# Trap_Lighting_Programmable_SpectrumV03B.net
KiCad netlist of a schematic drawn in EAGLE
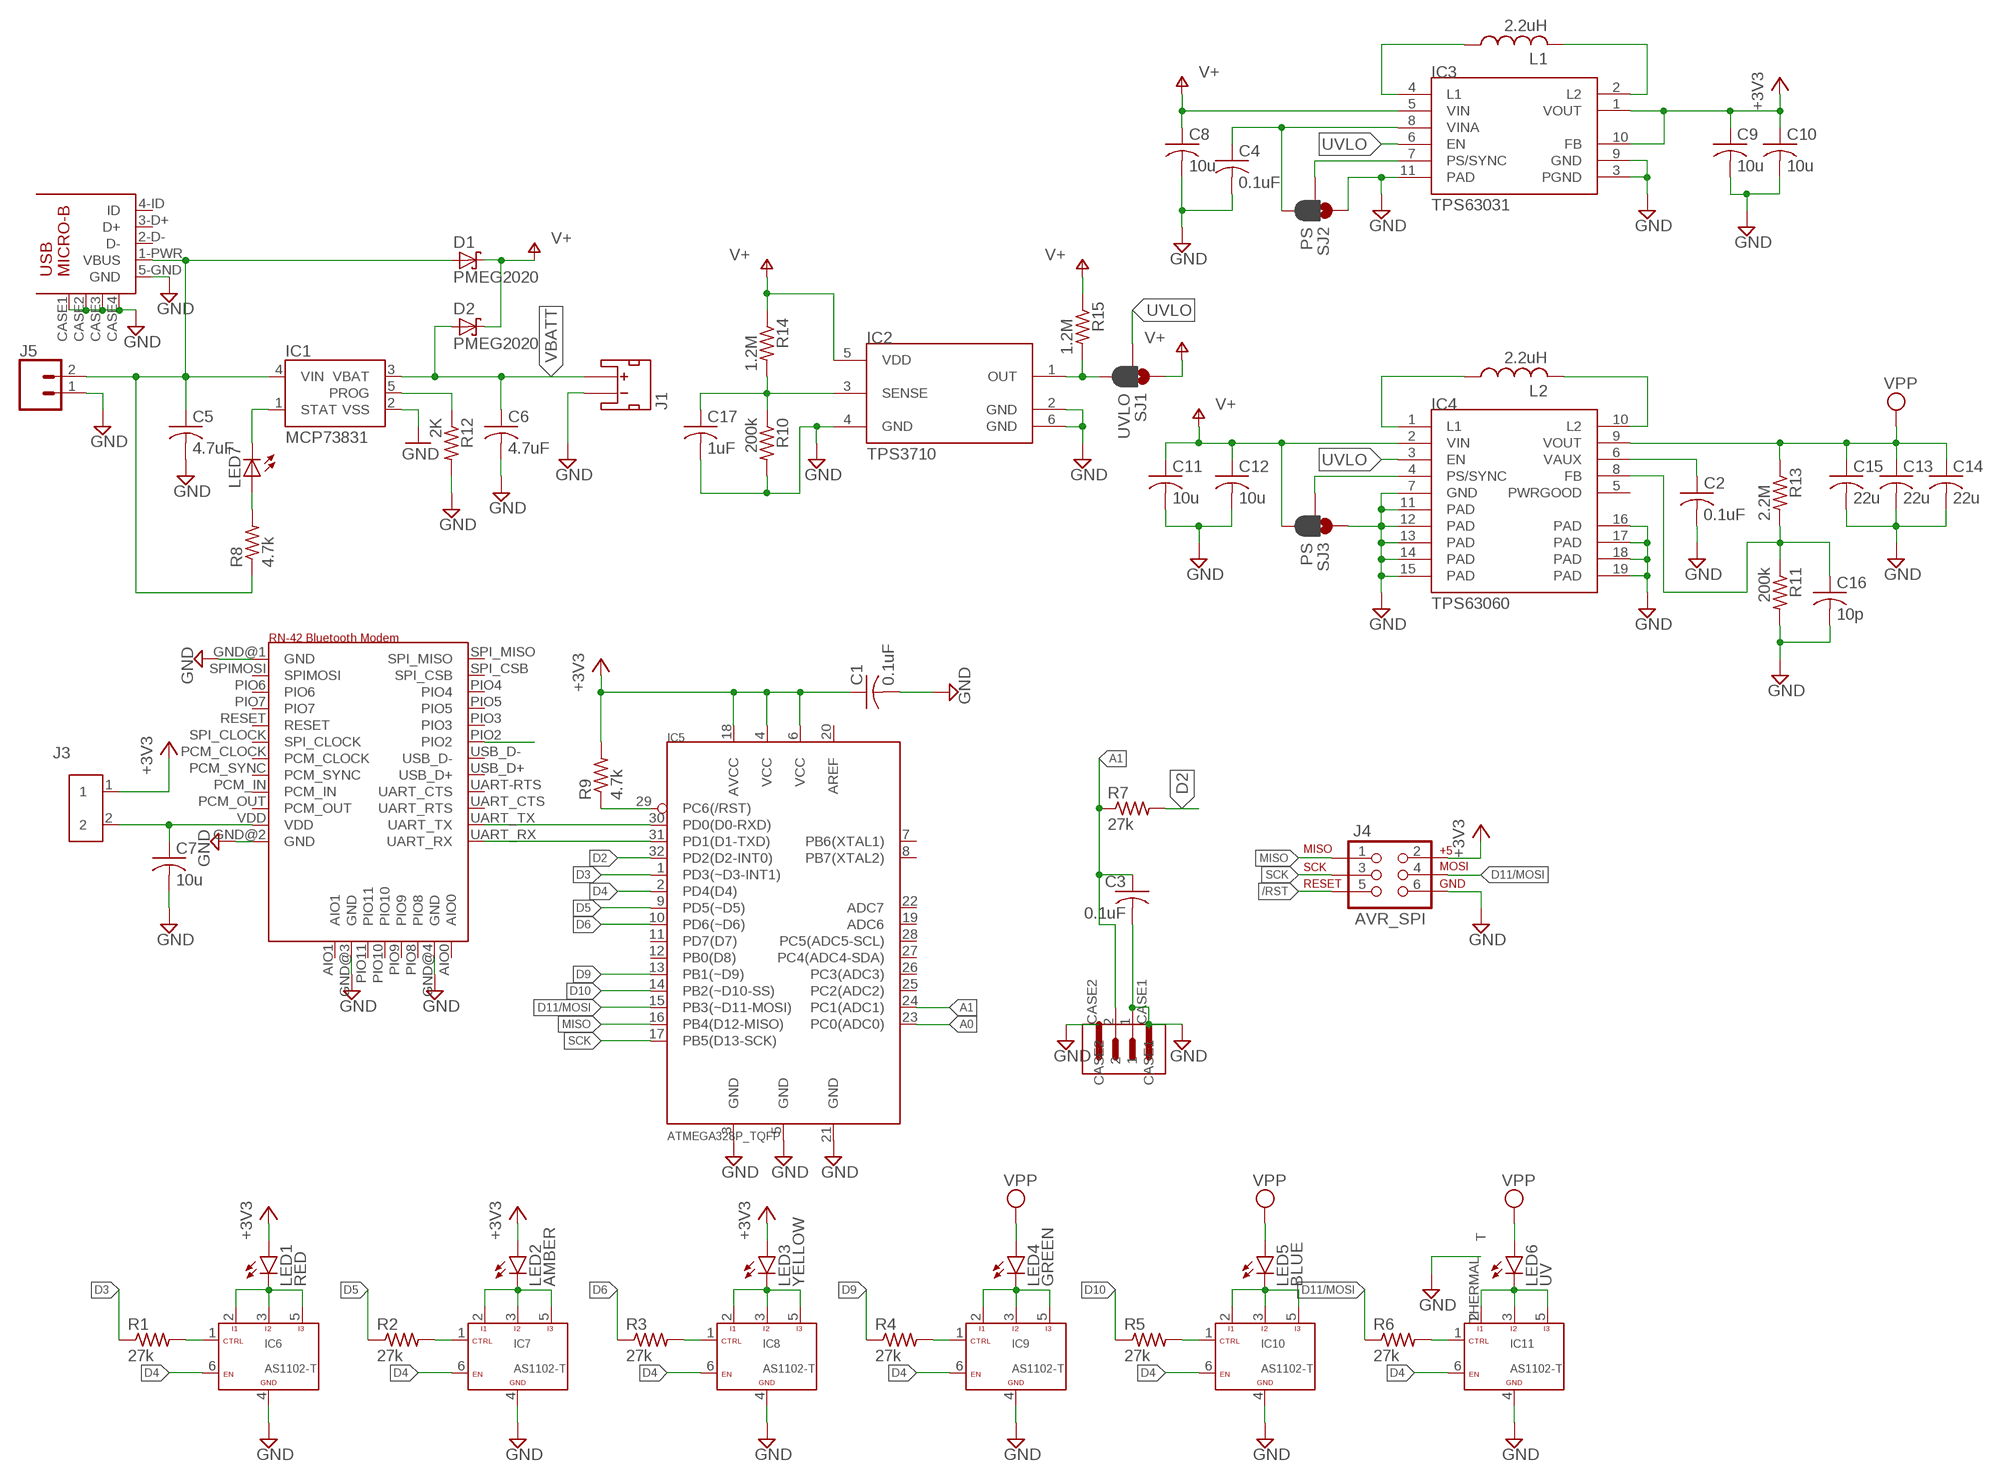
[diagram p0: schematic, sheet 1]

(export (version "E")
  (design (tool "Eeschema 10.0.6"))
  (components
    (comp (ref "A1")
      (value "RN-42_BLUETOOTH")
      (footprint "eagle-import:RN-42")
      (libsource (lib "eagle-import") (part "RN-42_BLUETOOTH"))
    )
    (comp (ref "C1")
      (value "0.1uF")
      (footprint "eagle-import:C0805")
      (libsource (lib "eagle-import") (part "C-USC0805"))
    )
    (comp (ref "C2")
      (value "0.1uF")
      (footprint "eagle-import:C0805")
      (libsource (lib "eagle-import") (part "C-USC0805"))
    )
    (comp (ref "C3")
      (value "0.1uF")
      (footprint "eagle-import:C0805")
      (libsource (lib "eagle-import") (part "C-USC0805"))
    )
    (comp (ref "C4")
      (value "0.1uF")
      (footprint "eagle-import:C0805")
      (libsource (lib "eagle-import") (part "C-USC0805"))
    )
    (comp (ref "C5")
      (value "4.7uF")
      (footprint "eagle-import:C0805")
      (libsource (lib "eagle-import") (part "C-USC0805"))
    )
    (comp (ref "C6")
      (value "4.7uF")
      (footprint "eagle-import:C0805")
      (libsource (lib "eagle-import") (part "C-USC0805"))
    )
    (comp (ref "C7")
      (value "10u")
      (footprint "eagle-import:C0805")
      (libsource (lib "eagle-import") (part "C-USC0805"))
    )
    (comp (ref "C8")
      (value "10u")
      (footprint "eagle-import:C0805")
      (libsource (lib "eagle-import") (part "C-USC0805"))
    )
    (comp (ref "C9")
      (value "10u")
      (footprint "eagle-import:C0805")
      (libsource (lib "eagle-import") (part "C-USC0805"))
    )
    (comp (ref "C10")
      (value "10u")
      (footprint "eagle-import:C0805")
      (libsource (lib "eagle-import") (part "C-USC0805"))
    )
    (comp (ref "C11")
      (value "10u")
      (footprint "eagle-import:C0805")
      (libsource (lib "eagle-import") (part "C-USC0805"))
    )
    (comp (ref "C12")
      (value "10u")
      (footprint "eagle-import:C0805")
      (libsource (lib "eagle-import") (part "C-USC0805"))
    )
    (comp (ref "C13")
      (value "22u")
      (footprint "eagle-import:C1206")
      (libsource (lib "eagle-import") (part "rcl_334_C-USC1206"))
    )
    (comp (ref "C14")
      (value "22u")
      (footprint "eagle-import:C1206")
      (libsource (lib "eagle-import") (part "rcl_334_C-USC1206"))
    )
    (comp (ref "C15")
      (value "22u")
      (footprint "eagle-import:C1206")
      (libsource (lib "eagle-import") (part "rcl_334_C-USC1206"))
    )
    (comp (ref "C16")
      (value "10p")
      (footprint "eagle-import:C0805")
      (libsource (lib "eagle-import") (part "C-USC0805"))
    )
    (comp (ref "C17")
      (value "1uF")
      (footprint "eagle-import:C0805")
      (libsource (lib "eagle-import") (part "C-USC0805"))
    )
    (comp (ref "D1")
      (value "PMEG2020")
      (footprint "eagle-import:SOD323_ST")
      (libsource (lib "eagle-import") (part "BAT60J"))
    )
    (comp (ref "D2")
      (value "PMEG2020")
      (footprint "eagle-import:SOD323_ST")
      (libsource (lib "eagle-import") (part "BAT60J"))
    )
    (comp (ref "IC1")
      (value "MCP73831")
      (footprint "eagle-import:SOT23-5")
      (libsource (lib "eagle-import") (part "MCP73831SMD"))
    )
    (comp (ref "IC2")
      (value "TPS3710")
      (footprint "eagle-import:SOT6")
      (libsource (lib "eagle-import") (part "TPS3710"))
    )
    (comp (ref "IC3")
      (value "TPS63031")
      (footprint "eagle-import:VSON-10")
      (libsource (lib "eagle-import") (part "TPS63031"))
    )
    (comp (ref "IC4")
      (value "TPS63060")
      (footprint "eagle-import:WSON1-10")
      (libsource (lib "eagle-import") (part "TPS63060"))
    )
    (comp (ref "IC5")
      (value "ATMEGA328P_TQFP")
      (footprint "eagle-import:TQFP-32")
      (libsource (lib "eagle-import") (part "ATMEGA328P_TQFP"))
    )
    (comp (ref "IC6")
      (value "AS1102-T")
      (footprint "eagle-import:SC70-6")
      (libsource (lib "eagle-import") (part "AS1102-T"))
    )
    (comp (ref "IC7")
      (value "AS1102-T")
      (footprint "eagle-import:SC70-6")
      (libsource (lib "eagle-import") (part "AS1102-T"))
    )
    (comp (ref "IC8")
      (value "AS1102-T")
      (footprint "eagle-import:SC70-6")
      (libsource (lib "eagle-import") (part "AS1102-T"))
    )
    (comp (ref "IC9")
      (value "AS1102-T")
      (footprint "eagle-import:SC70-6")
      (libsource (lib "eagle-import") (part "AS1102-T"))
    )
    (comp (ref "IC10")
      (value "AS1102-T")
      (footprint "eagle-import:SC70-6")
      (libsource (lib "eagle-import") (part "AS1102-T"))
    )
    (comp (ref "IC11")
      (value "AS1102-T")
      (footprint "eagle-import:SC70-6")
      (libsource (lib "eagle-import") (part "AS1102-T"))
    )
    (comp (ref "J1")
      (value "JST_2MM_MALE")
      (footprint "eagle-import:JST-2-SMD")
      (libsource (lib "eagle-import") (part "JST_2MM_MALE"))
    )
    (comp (ref "J2")
      (value "2PIN_SMD_PHOENIX_CONTACTVERTICAL_PACKAGE")
      (footprint "eagle-import:2-PIN-VERT-PHOENIX_SMD")
      (libsource (lib "eagle-import") (part "2PIN_SMD_PHOENIX_CONTACTVERTICAL_PACKAGE"))
    )
    (comp (ref "J3")
      (value "2MM_SMD_M_HEADER")
      (footprint "eagle-import:2MM_MALE_SMD_HEADER")
      (libsource (lib "eagle-import") (part "2MM_SMD_M_HEADER"))
    )
    (comp (ref "J4")
      (value "AVR_SPI")
      (footprint "eagle-import:2X3")
      (libsource (lib "eagle-import") (part "AVR_SPI_PRG_6PTH"))
    )
    (comp (ref "J5")
      (value "CONN_02PTH3")
      (footprint "eagle-import:1X02_LONGPADS")
      (libsource (lib "eagle-import") (part "CONN_02PTH3"))
    )
    (comp (ref "L1")
      (value "2.2uH")
      (footprint "eagle-import:VLF302512MT-2R2M-CA_INDUCTOR")
      (libsource (lib "eagle-import") (part "VLF302512MT-2R2M-CA_INDUCTOR"))
    )
    (comp (ref "L2")
      (value "2.2uH")
      (footprint "eagle-import:VLF302512MT-2R2M-CA_INDUCTOR")
      (libsource (lib "eagle-import") (part "VLF302512MT-2R2M-CA_INDUCTOR"))
    )
    (comp (ref "LED1")
      (value "RED")
      (footprint "eagle-import:LED_TT_OVS5MX")
      (libsource (lib "eagle-import") (part "LED_TT_OVS5MXTT_OVS5MX"))
    )
    (comp (ref "LED2")
      (value "AMBER")
      (footprint "eagle-import:LED_TT_OVS5MX")
      (libsource (lib "eagle-import") (part "LED_TT_OVS5MXTT_OVS5MX"))
    )
    (comp (ref "LED3")
      (value "YELLOW")
      (footprint "eagle-import:LED_TT_OVS5MX")
      (libsource (lib "eagle-import") (part "LED_TT_OVS5MXTT_OVS5MX"))
    )
    (comp (ref "LED4")
      (value "GREEN")
      (footprint "eagle-import:LED_LUXEON_3535L")
      (libsource (lib "eagle-import") (part "LED_TT_OVS5MXLUXEON_3535L"))
    )
    (comp (ref "LED5")
      (value "BLUE")
      (footprint "eagle-import:LED_TT_OVS5MX")
      (libsource (lib "eagle-import") (part "LED_TT_OVS5MXTT_OVS5MX"))
    )
    (comp (ref "LED6")
      (value "UV")
      (footprint "eagle-import:LED_LITEON_CO3_UV")
      (libsource (lib "eagle-import") (part "LITEON_CO34UV_LED"))
    )
    (comp (ref "LED7")
      (value "LEDCHIPLED_0805")
      (footprint "eagle-import:CHIPLED_0805")
      (libsource (lib "eagle-import") (part "LEDCHIPLED_0805"))
    )
    (comp (ref "R1")
      (value "27k")
      (footprint "eagle-import:R0805")
      (libsource (lib "eagle-import") (part "R-US_R0805"))
    )
    (comp (ref "R2")
      (value "27k")
      (footprint "eagle-import:R0805")
      (libsource (lib "eagle-import") (part "R-US_R0805"))
    )
    (comp (ref "R3")
      (value "27k")
      (footprint "eagle-import:R0805")
      (libsource (lib "eagle-import") (part "R-US_R0805"))
    )
    (comp (ref "R4")
      (value "27k")
      (footprint "eagle-import:R0805")
      (libsource (lib "eagle-import") (part "R-US_R0805"))
    )
    (comp (ref "R5")
      (value "27k")
      (footprint "eagle-import:R0805")
      (libsource (lib "eagle-import") (part "R-US_R0805"))
    )
    (comp (ref "R6")
      (value "27k")
      (footprint "eagle-import:R0805")
      (libsource (lib "eagle-import") (part "R-US_R0805"))
    )
    (comp (ref "R7")
      (value "27k")
      (footprint "eagle-import:R0805")
      (libsource (lib "eagle-import") (part "R-US_R0805"))
    )
    (comp (ref "R8")
      (value "4.7k")
      (footprint "eagle-import:R0805")
      (libsource (lib "eagle-import") (part "R-US_R0805"))
    )
    (comp (ref "R9")
      (value "4.7k")
      (footprint "eagle-import:R0805")
      (libsource (lib "eagle-import") (part "R-US_R0805"))
    )
    (comp (ref "R10")
      (value "200k")
      (footprint "eagle-import:R0805")
      (libsource (lib "eagle-import") (part "R-US_R0805"))
    )
    (comp (ref "R11")
      (value "200k")
      (footprint "eagle-import:R0805")
      (libsource (lib "eagle-import") (part "R-US_R0805"))
    )
    (comp (ref "R12")
      (value "2K")
      (footprint "eagle-import:R0805")
      (libsource (lib "eagle-import") (part "R-US_R0805"))
    )
    (comp (ref "R13")
      (value "2.2M")
      (footprint "eagle-import:R0805")
      (libsource (lib "eagle-import") (part "R-US_R0805"))
    )
    (comp (ref "R14")
      (value "1.2M")
      (footprint "eagle-import:R0805")
      (libsource (lib "eagle-import") (part "R-US_R0805"))
    )
    (comp (ref "R15")
      (value "1.2M")
      (footprint "eagle-import:R0805")
      (libsource (lib "eagle-import") (part "R-US_R0805"))
    )
    (comp (ref "SJ1")
      (value "UVLO")
      (footprint "eagle-import:SMT-JUMPER_3_1-NC_PASTE_SILK")
      (libsource (lib "eagle-import") (part "JUMPER-SMT_3_1-NC_PASTE_SILK"))
    )
    (comp (ref "SJ2")
      (value "PS")
      (footprint "eagle-import:SMT-JUMPER_3_1-NC_PASTE_SILK")
      (libsource (lib "eagle-import") (part "JUMPER-SMT_3_1-NC_PASTE_SILK"))
    )
    (comp (ref "SJ3")
      (value "PS")
      (footprint "eagle-import:SMT-JUMPER_3_1-NC_PASTE_SILK")
      (libsource (lib "eagle-import") (part "JUMPER-SMT_3_1-NC_PASTE_SILK"))
    )
    (comp (ref "USB1")
      (value "USB-MICRO-B")
      (footprint "eagle-import:USB_MICRO_B_WURTH_629105136821")
      (libsource (lib "eagle-import") (part "USB-MICRO-B"))
    )
  )
  (nets
    (net (code "1") (name "+3V3") (class "Default")
      (node (ref "C1") (pin "1") (pinfunction "1_1") (pintype "passive"))
      (node (ref "C10") (pin "1") (pinfunction "1_1") (pintype "passive"))
      (node (ref "C9") (pin "1") (pinfunction "1_1") (pintype "passive"))
      (node (ref "IC3") (pin "1") (pinfunction "VOUT_1") (pintype "passive"))
      (node (ref "IC3") (pin "10") (pinfunction "FB_10") (pintype "passive"))
      (node (ref "IC5") (pin "18") (pinfunction "AVCC_18") (pintype "bidirectional"))
      (node (ref "IC5") (pin "4") (pinfunction "VCC_4") (pintype "bidirectional"))
      (node (ref "IC5") (pin "6") (pinfunction "VCC_6") (pintype "bidirectional"))
      (node (ref "J3") (pin "1") (pinfunction "1_1") (pintype "bidirectional"))
      (node (ref "J4") (pin "2") (pinfunction "2_2") (pintype "passive"))
      (node (ref "LED1") (pin "A") (pinfunction "A_A") (pintype "passive"))
      (node (ref "LED2") (pin "A") (pinfunction "A_A") (pintype "passive"))
      (node (ref "LED3") (pin "A") (pinfunction "A_A") (pintype "passive"))
      (node (ref "R9") (pin "2") (pinfunction "2_2") (pintype "passive"))
    )
    (net (code "2") (name "A0") (class "Default")
      (node (ref "IC5") (pin "23") (pinfunction "PC0(ADC0)_23") (pintype "bidirectional"))
    )
    (net (code "3") (name "A1") (class "Default")
      (node (ref "C3") (pin "1") (pinfunction "1_1") (pintype "passive"))
      (node (ref "IC5") (pin "24") (pinfunction "PC1(ADC1)_24") (pintype "bidirectional"))
      (node (ref "J2") (pin "2") (pinfunction "2_2") (pintype "bidirectional"))
      (node (ref "R7") (pin "1") (pinfunction "1_1") (pintype "passive"))
    )
    (net (code "4") (name "D2") (class "Default")
      (node (ref "IC5") (pin "32") (pinfunction "PD2(D2-INT0)_32") (pintype "bidirectional"))
      (node (ref "R7") (pin "2") (pinfunction "2_2") (pintype "passive"))
    )
    (net (code "5") (name "D3") (class "Default")
      (node (ref "IC5") (pin "1") (pinfunction "PD3(~{D3-INT1})_1") (pintype "bidirectional"))
      (node (ref "R1") (pin "1") (pinfunction "1_1") (pintype "passive"))
    )
    (net (code "6") (name "D4") (class "Default")
      (node (ref "IC10") (pin "6") (pinfunction "EN_6") (pintype "bidirectional"))
      (node (ref "IC11") (pin "6") (pinfunction "EN_6") (pintype "bidirectional"))
      (node (ref "IC5") (pin "2") (pinfunction "PD4(D4)_2") (pintype "bidirectional"))
      (node (ref "IC6") (pin "6") (pinfunction "EN_6") (pintype "bidirectional"))
      (node (ref "IC7") (pin "6") (pinfunction "EN_6") (pintype "bidirectional"))
      (node (ref "IC8") (pin "6") (pinfunction "EN_6") (pintype "bidirectional"))
      (node (ref "IC9") (pin "6") (pinfunction "EN_6") (pintype "bidirectional"))
    )
    (net (code "7") (name "D5") (class "Default")
      (node (ref "IC5") (pin "9") (pinfunction "PD5(~{D5})_9") (pintype "bidirectional"))
      (node (ref "R2") (pin "1") (pinfunction "1_1") (pintype "passive"))
    )
    (net (code "8") (name "D6") (class "Default")
      (node (ref "IC5") (pin "10") (pinfunction "PD6(~{D6})_10") (pintype "bidirectional"))
      (node (ref "R3") (pin "1") (pinfunction "1_1") (pintype "passive"))
    )
    (net (code "9") (name "D9") (class "Default")
      (node (ref "IC5") (pin "13") (pinfunction "PB1(~{D9})_13") (pintype "bidirectional"))
      (node (ref "R4") (pin "1") (pinfunction "1_1") (pintype "passive"))
    )
    (net (code "10") (name "D10") (class "Default")
      (node (ref "IC5") (pin "14") (pinfunction "PB2(~{D10-SS})_14") (pintype "bidirectional"))
      (node (ref "R5") (pin "1") (pinfunction "1_1") (pintype "passive"))
    )
    (net (code "11") (name "D11{slash}MOSI") (class "Default")
      (node (ref "IC5") (pin "15") (pinfunction "PB3(~{D11-MOSI})_15") (pintype "bidirectional"))
      (node (ref "J4") (pin "4") (pinfunction "4_4") (pintype "passive"))
      (node (ref "R6") (pin "1") (pinfunction "1_1") (pintype "passive"))
    )
    (net (code "12") (name "GND") (class "Default")
      (node (ref "A1") (pin "GND@1") (pinfunction "GND_GND@1") (pintype "bidirectional"))
      (node (ref "A1") (pin "GND@2") (pinfunction "GND_GND@2") (pintype "bidirectional"))
      (node (ref "A1") (pin "GND@3") (pinfunction "GND_GND@3") (pintype "bidirectional"))
      (node (ref "A1") (pin "GND@4") (pinfunction "GND_GND@4") (pintype "bidirectional"))
      (node (ref "C1") (pin "2") (pinfunction "2_2") (pintype "passive"))
      (node (ref "C10") (pin "2") (pinfunction "2_2") (pintype "passive"))
      (node (ref "C11") (pin "2") (pinfunction "2_2") (pintype "passive"))
      (node (ref "C12") (pin "2") (pinfunction "2_2") (pintype "passive"))
      (node (ref "C13") (pin "2") (pinfunction "2_2") (pintype "passive"))
      (node (ref "C14") (pin "2") (pinfunction "2_2") (pintype "passive"))
      (node (ref "C15") (pin "2") (pinfunction "2_2") (pintype "passive"))
      (node (ref "C16") (pin "2") (pinfunction "2_2") (pintype "passive"))
      (node (ref "C17") (pin "2") (pinfunction "2_2") (pintype "passive"))
      (node (ref "C2") (pin "2") (pinfunction "2_2") (pintype "passive"))
      (node (ref "C3") (pin "2") (pinfunction "2_2") (pintype "passive"))
      (node (ref "C4") (pin "2") (pinfunction "2_2") (pintype "passive"))
      (node (ref "C5") (pin "2") (pinfunction "2_2") (pintype "passive"))
      (node (ref "C6") (pin "2") (pinfunction "2_2") (pintype "passive"))
      (node (ref "C7") (pin "2") (pinfunction "2_2") (pintype "passive"))
      (node (ref "C8") (pin "2") (pinfunction "2_2") (pintype "passive"))
      (node (ref "C9") (pin "2") (pinfunction "2_2") (pintype "passive"))
      (node (ref "IC1") (pin "2") (pinfunction "VSS_2") (pintype "power_in"))
      (node (ref "IC10") (pin "4") (pinfunction "GND_4") (pintype "bidirectional"))
      (node (ref "IC11") (pin "4") (pinfunction "GND_4") (pintype "bidirectional"))
      (node (ref "IC2") (pin "2") (pinfunction "GND_2") (pintype "power_in"))
      (node (ref "IC2") (pin "4") (pinfunction "GND_4") (pintype "power_in"))
      (node (ref "IC2") (pin "6") (pinfunction "GND_6") (pintype "power_in"))
      (node (ref "IC3") (pin "11") (pinfunction "PAD_11") (pintype "power_in"))
      (node (ref "IC3") (pin "3") (pinfunction "PGND_3") (pintype "power_in"))
      (node (ref "IC3") (pin "9") (pinfunction "GND_9") (pintype "power_in"))
      (node (ref "IC4") (pin "11") (pinfunction "PAD_11") (pintype "power_in"))
      (node (ref "IC4") (pin "12") (pinfunction "PAD_12") (pintype "power_in"))
      (node (ref "IC4") (pin "13") (pinfunction "PAD_13") (pintype "power_in"))
      (node (ref "IC4") (pin "14") (pinfunction "PAD_14") (pintype "power_in"))
      (node (ref "IC4") (pin "15") (pinfunction "PAD_15") (pintype "power_in"))
      (node (ref "IC4") (pin "16") (pinfunction "PAD_16") (pintype "power_in"))
      (node (ref "IC4") (pin "17") (pinfunction "PAD_17") (pintype "power_in"))
      (node (ref "IC4") (pin "18") (pinfunction "PAD_18") (pintype "power_in"))
      (node (ref "IC4") (pin "19") (pinfunction "PAD_19") (pintype "power_in"))
      (node (ref "IC4") (pin "7") (pinfunction "GND_7") (pintype "power_in"))
      (node (ref "IC5") (pin "21") (pinfunction "GND_21") (pintype "bidirectional"))
      (node (ref "IC5") (pin "3") (pinfunction "GND_3") (pintype "bidirectional"))
      (node (ref "IC5") (pin "5") (pinfunction "GND_5") (pintype "bidirectional"))
      (node (ref "IC6") (pin "4") (pinfunction "GND_4") (pintype "bidirectional"))
      (node (ref "IC7") (pin "4") (pinfunction "GND_4") (pintype "bidirectional"))
      (node (ref "IC8") (pin "4") (pinfunction "GND_4") (pintype "bidirectional"))
      (node (ref "IC9") (pin "4") (pinfunction "GND_4") (pintype "bidirectional"))
      (node (ref "J1") (pin "1") (pinfunction "-_1") (pintype "bidirectional"))
      (node (ref "J2") (pin "1") (pinfunction "1_1") (pintype "bidirectional"))
      (node (ref "J2") (pin "CASE1") (pinfunction "CASE1_CASE1") (pintype "bidirectional"))
      (node (ref "J2") (pin "CASE2") (pinfunction "CASE2_CASE2") (pintype "bidirectional"))
      (node (ref "J4") (pin "6") (pinfunction "6_6") (pintype "passive"))
      (node (ref "J5") (pin "1") (pinfunction "1_1") (pintype "passive"))
      (node (ref "LED6") (pin "THERMAL") (pinfunction "T_THERMAL") (pintype "bidirectional"))
      (node (ref "R10") (pin "2") (pinfunction "2_2") (pintype "passive"))
      (node (ref "R11") (pin "2") (pinfunction "2_2") (pintype "passive"))
      (node (ref "R12") (pin "2") (pinfunction "2_2") (pintype "passive"))
      (node (ref "SJ2") (pin "1") (pinfunction "1_1") (pintype "passive"))
      (node (ref "SJ3") (pin "1") (pinfunction "1_1") (pintype "passive"))
      (node (ref "USB1") (pin "5-GND") (pinfunction "GND_5-GND") (pintype "power_in"))
      (node (ref "USB1") (pin "CASE1") (pinfunction "CASE_CASE1") (pintype "bidirectional"))
      (node (ref "USB1") (pin "CASE2") (pinfunction "CASE_CASE2") (pintype "bidirectional"))
      (node (ref "USB1") (pin "CASE3") (pinfunction "CASE_CASE3") (pintype "bidirectional"))
      (node (ref "USB1") (pin "CASE4") (pinfunction "CASE_CASE4") (pintype "bidirectional"))
    )
    (net (code "13") (name "MISO") (class "Default")
      (node (ref "IC5") (pin "16") (pinfunction "PB4(D12-MISO)_16") (pintype "bidirectional"))
      (node (ref "J4") (pin "1") (pinfunction "1_1") (pintype "passive"))
    )
    (net (code "14") (name "Net-(A1-PadVDD)") (class "Default")
      (node (ref "A1") (pin "VDD") (pinfunction "VDD_VDD") (pintype "bidirectional"))
      (node (ref "C7") (pin "1") (pinfunction "1_1") (pintype "passive"))
      (node (ref "J3") (pin "2") (pinfunction "2_2") (pintype "bidirectional"))
    )
    (net (code "15") (name "Net-(IC1-PROG)") (class "Default")
      (node (ref "IC1") (pin "5") (pinfunction "PROG_5") (pintype "input"))
      (node (ref "R12") (pin "1") (pinfunction "1_1") (pintype "passive"))
    )
    (net (code "16") (name "Net-(IC1-STAT)") (class "Default")
      (node (ref "IC1") (pin "1") (pinfunction "STAT_1") (pintype "output"))
      (node (ref "LED7") (pin "C") (pinfunction "C_C") (pintype "passive"))
    )
    (net (code "17") (name "Net-(IC1-VIN)") (class "Default")
      (node (ref "C5") (pin "1") (pinfunction "1_1") (pintype "passive"))
      (node (ref "D1") (pin "A") (pinfunction "A_A") (pintype "passive"))
      (node (ref "IC1") (pin "4") (pinfunction "VIN_4") (pintype "power_in"))
      (node (ref "J5") (pin "2") (pinfunction "2_2") (pintype "passive"))
      (node (ref "R8") (pin "1") (pinfunction "1_1") (pintype "passive"))
      (node (ref "USB1") (pin "1-PWR") (pinfunction "VBUS_1-PWR") (pintype "power_in"))
    )
    (net (code "18") (name "Net-(IC2-OUT)") (class "Default")
      (node (ref "IC2") (pin "1") (pinfunction "OUT_1") (pintype "passive"))
      (node (ref "R15") (pin "2") (pinfunction "2_2") (pintype "passive"))
      (node (ref "SJ1") (pin "3") (pinfunction "3_3") (pintype "passive"))
    )
    (net (code "19") (name "Net-(IC2-SENSE)") (class "Default")
      (node (ref "C17") (pin "1") (pinfunction "1_1") (pintype "passive"))
      (node (ref "IC2") (pin "3") (pinfunction "SENSE_3") (pintype "passive"))
      (node (ref "R10") (pin "1") (pinfunction "1_1") (pintype "passive"))
      (node (ref "R14") (pin "2") (pinfunction "2_2") (pintype "passive"))
    )
    (net (code "20") (name "Net-(IC3-L1)") (class "Default")
      (node (ref "IC3") (pin "4") (pinfunction "L1_4") (pintype "passive"))
      (node (ref "L1") (pin "1") (pinfunction "1_1") (pintype "passive"))
    )
    (net (code "21") (name "Net-(IC3-L2)") (class "Default")
      (node (ref "IC3") (pin "2") (pinfunction "L2_2") (pintype "passive"))
      (node (ref "L1") (pin "2") (pinfunction "2_2") (pintype "passive"))
    )
    (net (code "22") (name "Net-(IC3-PS{slash}SYNC)") (class "Default")
      (node (ref "IC3") (pin "7") (pinfunction "PS/SYNC_7") (pintype "input"))
      (node (ref "SJ2") (pin "2") (pinfunction "2_2") (pintype "passive"))
    )
    (net (code "23") (name "Net-(IC3-VINA)") (class "Default")
      (node (ref "C4") (pin "1") (pinfunction "1_1") (pintype "passive"))
      (node (ref "IC3") (pin "8") (pinfunction "VINA_8") (pintype "passive"))
      (node (ref "SJ2") (pin "3") (pinfunction "3_3") (pintype "passive"))
    )
    (net (code "24") (name "Net-(IC4-FB)") (class "Default")
      (node (ref "C16") (pin "1") (pinfunction "1_1") (pintype "passive"))
      (node (ref "IC4") (pin "8") (pinfunction "FB_8") (pintype "passive"))
      (node (ref "R11") (pin "1") (pinfunction "1_1") (pintype "passive"))
      (node (ref "R13") (pin "2") (pinfunction "2_2") (pintype "passive"))
    )
    (net (code "25") (name "Net-(IC4-L1)") (class "Default")
      (node (ref "IC4") (pin "1") (pinfunction "L1_1") (pintype "passive"))
      (node (ref "L2") (pin "1") (pinfunction "1_1") (pintype "passive"))
    )
    (net (code "26") (name "Net-(IC4-L2)") (class "Default")
      (node (ref "IC4") (pin "10") (pinfunction "L2_10") (pintype "passive"))
      (node (ref "L2") (pin "2") (pinfunction "2_2") (pintype "passive"))
    )
    (net (code "27") (name "Net-(IC4-PS{slash}SYNC)") (class "Default")
      (node (ref "IC4") (pin "4") (pinfunction "PS/SYNC_4") (pintype "input"))
      (node (ref "SJ3") (pin "2") (pinfunction "2_2") (pintype "passive"))
    )
    (net (code "28") (name "Net-(IC4-VAUX)") (class "Default")
      (node (ref "C2") (pin "1") (pinfunction "1_1") (pintype "passive"))
      (node (ref "IC4") (pin "6") (pinfunction "VAUX_6") (pintype "passive"))
    )
    (net (code "29") (name "Net-(IC5-PD0(D0-RXD))") (class "Default")
      (node (ref "A1") (pin "UART_TX") (pinfunction "UART_TX_UART_TX") (pintype "bidirectional"))
      (node (ref "IC5") (pin "30") (pinfunction "PD0(D0-RXD)_30") (pintype "bidirectional"))
    )
    (net (code "30") (name "Net-(IC5-PD1(D1-TXD))") (class "Default")
      (node (ref "A1") (pin "UART_RX") (pinfunction "UART_RX_UART_RX") (pintype "bidirectional"))
      (node (ref "IC5") (pin "31") (pinfunction "PD1(D1-TXD)_31") (pintype "bidirectional"))
    )
    (net (code "31") (name "Net-(IC6-CTRL)") (class "Default")
      (node (ref "IC6") (pin "1") (pinfunction "CTRL_1") (pintype "bidirectional"))
      (node (ref "R1") (pin "2") (pinfunction "2_2") (pintype "passive"))
    )
    (net (code "32") (name "Net-(IC6-I1)") (class "Default")
      (node (ref "IC6") (pin "2") (pinfunction "I1_2") (pintype "bidirectional"))
      (node (ref "IC6") (pin "3") (pinfunction "I2_3") (pintype "bidirectional"))
      (node (ref "IC6") (pin "5") (pinfunction "I3_5") (pintype "bidirectional"))
      (node (ref "LED1") (pin "C") (pinfunction "C_C") (pintype "passive"))
    )
    (net (code "33") (name "Net-(IC7-CTRL)") (class "Default")
      (node (ref "IC7") (pin "1") (pinfunction "CTRL_1") (pintype "bidirectional"))
      (node (ref "R2") (pin "2") (pinfunction "2_2") (pintype "passive"))
    )
    (net (code "34") (name "Net-(IC7-I1)") (class "Default")
      (node (ref "IC7") (pin "2") (pinfunction "I1_2") (pintype "bidirectional"))
      (node (ref "IC7") (pin "3") (pinfunction "I2_3") (pintype "bidirectional"))
      (node (ref "IC7") (pin "5") (pinfunction "I3_5") (pintype "bidirectional"))
      (node (ref "LED2") (pin "C") (pinfunction "C_C") (pintype "passive"))
    )
    (net (code "35") (name "Net-(IC8-CTRL)") (class "Default")
      (node (ref "IC8") (pin "1") (pinfunction "CTRL_1") (pintype "bidirectional"))
      (node (ref "R3") (pin "2") (pinfunction "2_2") (pintype "passive"))
    )
    (net (code "36") (name "Net-(IC8-I1)") (class "Default")
      (node (ref "IC8") (pin "2") (pinfunction "I1_2") (pintype "bidirectional"))
      (node (ref "IC8") (pin "3") (pinfunction "I2_3") (pintype "bidirectional"))
      (node (ref "IC8") (pin "5") (pinfunction "I3_5") (pintype "bidirectional"))
      (node (ref "LED3") (pin "C") (pinfunction "C_C") (pintype "passive"))
    )
    (net (code "37") (name "Net-(IC9-CTRL)") (class "Default")
      (node (ref "IC9") (pin "1") (pinfunction "CTRL_1") (pintype "bidirectional"))
      (node (ref "R4") (pin "2") (pinfunction "2_2") (pintype "passive"))
    )
    (net (code "38") (name "Net-(IC9-I1)") (class "Default")
      (node (ref "IC9") (pin "2") (pinfunction "I1_2") (pintype "bidirectional"))
      (node (ref "IC9") (pin "3") (pinfunction "I2_3") (pintype "bidirectional"))
      (node (ref "IC9") (pin "5") (pinfunction "I3_5") (pintype "bidirectional"))
      (node (ref "LED4") (pin "C") (pinfunction "C_C") (pintype "passive"))
    )
    (net (code "39") (name "Net-(IC10-CTRL)") (class "Default")
      (node (ref "IC10") (pin "1") (pinfunction "CTRL_1") (pintype "bidirectional"))
      (node (ref "R5") (pin "2") (pinfunction "2_2") (pintype "passive"))
    )
    (net (code "40") (name "Net-(IC10-I1)") (class "Default")
      (node (ref "IC10") (pin "2") (pinfunction "I1_2") (pintype "bidirectional"))
      (node (ref "IC10") (pin "3") (pinfunction "I2_3") (pintype "bidirectional"))
      (node (ref "IC10") (pin "5") (pinfunction "I3_5") (pintype "bidirectional"))
      (node (ref "LED5") (pin "C") (pinfunction "C_C") (pintype "passive"))
    )
    (net (code "41") (name "Net-(IC11-CTRL)") (class "Default")
      (node (ref "IC11") (pin "1") (pinfunction "CTRL_1") (pintype "bidirectional"))
      (node (ref "R6") (pin "2") (pinfunction "2_2") (pintype "passive"))
    )
    (net (code "42") (name "Net-(IC11-I1)") (class "Default")
      (node (ref "IC11") (pin "2") (pinfunction "I1_2") (pintype "bidirectional"))
      (node (ref "IC11") (pin "3") (pinfunction "I2_3") (pintype "bidirectional"))
      (node (ref "IC11") (pin "5") (pinfunction "I3_5") (pintype "bidirectional"))
      (node (ref "LED6") (pin "K") (pinfunction "C_K") (pintype "passive"))
    )
    (net (code "43") (name "Net-(LED7-PadA)") (class "Default")
      (node (ref "LED7") (pin "A") (pinfunction "A_A") (pintype "passive"))
      (node (ref "R8") (pin "2") (pinfunction "2_2") (pintype "passive"))
    )
    (net (code "44") (name "SCK") (class "Default")
      (node (ref "IC5") (pin "17") (pinfunction "PB5(D13-SCK)_17") (pintype "bidirectional"))
      (node (ref "J4") (pin "3") (pinfunction "3_3") (pintype "passive"))
    )
    (net (code "45") (name "UVLO") (class "Default")
      (node (ref "IC3") (pin "6") (pinfunction "EN_6") (pintype "input"))
      (node (ref "IC4") (pin "3") (pinfunction "EN_3") (pintype "input"))
      (node (ref "SJ1") (pin "2") (pinfunction "2_2") (pintype "passive"))
    )
    (net (code "46") (name "V+") (class "Default")
      (node (ref "C11") (pin "1") (pinfunction "1_1") (pintype "passive"))
      (node (ref "C12") (pin "1") (pinfunction "1_1") (pintype "passive"))
      (node (ref "C8") (pin "1") (pinfunction "1_1") (pintype "passive"))
      (node (ref "D1") (pin "C") (pinfunction "C_C") (pintype "passive"))
      (node (ref "D2") (pin "C") (pinfunction "C_C") (pintype "passive"))
      (node (ref "IC2") (pin "5") (pinfunction "VDD_5") (pintype "power_in"))
      (node (ref "IC3") (pin "5") (pinfunction "VIN_5") (pintype "power_in"))
      (node (ref "IC4") (pin "2") (pinfunction "VIN_2") (pintype "power_in"))
      (node (ref "R14") (pin "1") (pinfunction "1_1") (pintype "passive"))
      (node (ref "R15") (pin "1") (pinfunction "1_1") (pintype "passive"))
      (node (ref "SJ1") (pin "1") (pinfunction "1_1") (pintype "passive"))
      (node (ref "SJ3") (pin "3") (pinfunction "3_3") (pintype "passive"))
    )
    (net (code "47") (name "VBATT") (class "Default")
      (node (ref "C6") (pin "1") (pinfunction "1_1") (pintype "passive"))
      (node (ref "D2") (pin "A") (pinfunction "A_A") (pintype "passive"))
      (node (ref "IC1") (pin "3") (pinfunction "VBAT_3") (pintype "power_in"))
      (node (ref "J1") (pin "2") (pinfunction "+_2") (pintype "bidirectional"))
    )
    (net (code "48") (name "VPP") (class "Default")
      (node (ref "C13") (pin "1") (pinfunction "1_1") (pintype "passive"))
      (node (ref "C14") (pin "1") (pinfunction "1_1") (pintype "passive"))
      (node (ref "C15") (pin "1") (pinfunction "1_1") (pintype "passive"))
      (node (ref "IC4") (pin "9") (pinfunction "VOUT_9") (pintype "passive"))
      (node (ref "LED4") (pin "A") (pinfunction "A_A") (pintype "passive"))
      (node (ref "LED5") (pin "A") (pinfunction "A_A") (pintype "passive"))
      (node (ref "LED6") (pin "A") (pinfunction "A_A") (pintype "passive"))
      (node (ref "R13") (pin "1") (pinfunction "1_1") (pintype "passive"))
    )
    (net (code "49") (name "unconnected-(A1-PadAIO0)") (class "Default")
      (node (ref "A1") (pin "AIO0") (pinfunction "AIO0_AIO0") (pintype "bidirectional"))
    )
    (net (code "50") (name "unconnected-(A1-PadAIO1)") (class "Default")
      (node (ref "A1") (pin "AIO1") (pinfunction "AIO1_AIO1") (pintype "bidirectional"))
    )
    (net (code "51") (name "unconnected-(A1-PadPCM_CLOCK)") (class "Default")
      (node (ref "A1") (pin "PCM_CLOCK") (pinfunction "PCM_CLOCK_PCM_CLOCK") (pintype "bidirectional"))
    )
    (net (code "52") (name "unconnected-(A1-PadPCM_IN)") (class "Default")
      (node (ref "A1") (pin "PCM_IN") (pinfunction "PCM_IN_PCM_IN") (pintype "bidirectional"))
    )
    (net (code "53") (name "unconnected-(A1-PadPCM_OUT)") (class "Default")
      (node (ref "A1") (pin "PCM_OUT") (pinfunction "PCM_OUT_PCM_OUT") (pintype "bidirectional"))
    )
    (net (code "54") (name "unconnected-(A1-PadPCM_SYNC)") (class "Default")
      (node (ref "A1") (pin "PCM_SYNC") (pinfunction "PCM_SYNC_PCM_SYNC") (pintype "bidirectional"))
    )
    (net (code "55") (name "unconnected-(A1-PadPIO2)") (class "Default")
      (node (ref "A1") (pin "PIO2") (pinfunction "PIO2_PIO2") (pintype "bidirectional"))
    )
    (net (code "56") (name "unconnected-(A1-PadPIO3)") (class "Default")
      (node (ref "A1") (pin "PIO3") (pinfunction "PIO3_PIO3") (pintype "bidirectional"))
    )
    (net (code "57") (name "unconnected-(A1-PadPIO4)") (class "Default")
      (node (ref "A1") (pin "PIO4") (pinfunction "PIO4_PIO4") (pintype "bidirectional"))
    )
    (net (code "58") (name "unconnected-(A1-PadPIO5)") (class "Default")
      (node (ref "A1") (pin "PIO5") (pinfunction "PIO5_PIO5") (pintype "bidirectional"))
    )
    (net (code "59") (name "unconnected-(A1-PadPIO6)") (class "Default")
      (node (ref "A1") (pin "PIO6") (pinfunction "PIO6_PIO6") (pintype "bidirectional"))
    )
    (net (code "60") (name "unconnected-(A1-PadPIO7)") (class "Default")
      (node (ref "A1") (pin "PIO7") (pinfunction "PIO7_PIO7") (pintype "bidirectional"))
    )
    (net (code "61") (name "unconnected-(A1-PadPIO8)") (class "Default")
      (node (ref "A1") (pin "PIO8") (pinfunction "PIO8_PIO8") (pintype "bidirectional"))
    )
    (net (code "62") (name "unconnected-(A1-PadPIO9)") (class "Default")
      (node (ref "A1") (pin "PIO9") (pinfunction "PIO9_PIO9") (pintype "bidirectional"))
    )
    (net (code "63") (name "unconnected-(A1-PadPIO10)") (class "Default")
      (node (ref "A1") (pin "PIO10") (pinfunction "PIO10_PIO10") (pintype "bidirectional"))
    )
    (net (code "64") (name "unconnected-(A1-PadPIO11)") (class "Default")
      (node (ref "A1") (pin "PIO11") (pinfunction "PIO11_PIO11") (pintype "bidirectional"))
    )
    (net (code "65") (name "unconnected-(A1-PadRESET)") (class "Default")
      (node (ref "A1") (pin "RESET") (pinfunction "RESET_RESET") (pintype "bidirectional"))
    )
    (net (code "66") (name "unconnected-(A1-PadSPIMOSI)") (class "Default")
      (node (ref "A1") (pin "SPIMOSI") (pinfunction "SPIMOSI_SPIMOSI") (pintype "bidirectional"))
    )
    (net (code "67") (name "unconnected-(A1-PadSPI_CLOCK)") (class "Default")
      (node (ref "A1") (pin "SPI_CLOCK") (pinfunction "SPI_CLOCK_SPI_CLOCK") (pintype "bidirectional"))
    )
    (net (code "68") (name "unconnected-(A1-PadSPI_CSB)") (class "Default")
      (node (ref "A1") (pin "SPI_CSB") (pinfunction "SPI_CSB_SPI_CSB") (pintype "bidirectional"))
    )
    (net (code "69") (name "unconnected-(A1-PadSPI_MISO)") (class "Default")
      (node (ref "A1") (pin "SPI_MISO") (pinfunction "SPI_MISO_SPI_MISO") (pintype "bidirectional"))
    )
    (net (code "70") (name "unconnected-(A1-PadUSB_D+)") (class "Default")
      (node (ref "A1") (pin "USB_D+") (pinfunction "USB_D+_USB_D+") (pintype "bidirectional"))
    )
    (net (code "71") (name "unconnected-(A1-PadUSB_D-)") (class "Default")
      (node (ref "A1") (pin "USB_D-") (pinfunction "USB_D-_USB_D-") (pintype "bidirectional"))
    )
    (net (code "72") (name "unconnected-(A1-UART_CTS-PadUART-RTS)") (class "Default")
      (node (ref "A1") (pin "UART-RTS") (pinfunction "UART_CTS_UART-RTS") (pintype "bidirectional"))
    )
    (net (code "73") (name "unconnected-(A1-UART_RTS-PadUART_CTS)") (class "Default")
      (node (ref "A1") (pin "UART_CTS") (pinfunction "UART_RTS_UART_CTS") (pintype "bidirectional"))
    )
    (net (code "74") (name "unconnected-(IC4-PWRGOOD-Pad5)") (class "Default")
      (node (ref "IC4") (pin "5") (pinfunction "PWRGOOD_5") (pintype "passive"))
    )
    (net (code "75") (name "unconnected-(IC5-ADC6-Pad19)") (class "Default")
      (node (ref "IC5") (pin "19") (pinfunction "ADC6_19") (pintype "bidirectional"))
    )
    (net (code "76") (name "unconnected-(IC5-ADC7-Pad22)") (class "Default")
      (node (ref "IC5") (pin "22") (pinfunction "ADC7_22") (pintype "bidirectional"))
    )
    (net (code "77") (name "unconnected-(IC5-AREF-Pad20)") (class "Default")
      (node (ref "IC5") (pin "20") (pinfunction "AREF_20") (pintype "bidirectional"))
    )
    (net (code "78") (name "unconnected-(IC5-PB0(D8)-Pad12)") (class "Default")
      (node (ref "IC5") (pin "12") (pinfunction "PB0(D8)_12") (pintype "bidirectional"))
    )
    (net (code "79") (name "unconnected-(IC5-PB6(XTAL1)-Pad7)") (class "Default")
      (node (ref "IC5") (pin "7") (pinfunction "PB6(XTAL1)_7") (pintype "bidirectional"))
    )
    (net (code "80") (name "unconnected-(IC5-PB7(XTAL2)-Pad8)") (class "Default")
      (node (ref "IC5") (pin "8") (pinfunction "PB7(XTAL2)_8") (pintype "bidirectional"))
    )
    (net (code "81") (name "unconnected-(IC5-PC2(ADC2)-Pad25)") (class "Default")
      (node (ref "IC5") (pin "25") (pinfunction "PC2(ADC2)_25") (pintype "bidirectional"))
    )
    (net (code "82") (name "unconnected-(IC5-PC3(ADC3)-Pad26)") (class "Default")
      (node (ref "IC5") (pin "26") (pinfunction "PC3(ADC3)_26") (pintype "bidirectional"))
    )
    (net (code "83") (name "unconnected-(IC5-PC4(ADC4-SDA)-Pad27)") (class "Default")
      (node (ref "IC5") (pin "27") (pinfunction "PC4(ADC4-SDA)_27") (pintype "bidirectional"))
    )
    (net (code "84") (name "unconnected-(IC5-PC5(ADC5-SCL)-Pad28)") (class "Default")
      (node (ref "IC5") (pin "28") (pinfunction "PC5(ADC5-SCL)_28") (pintype "bidirectional"))
    )
    (net (code "85") (name "unconnected-(IC5-PD7(D7)-Pad11)") (class "Default")
      (node (ref "IC5") (pin "11") (pinfunction "PD7(D7)_11") (pintype "bidirectional"))
    )
    (net (code "86") (name "unconnected-(J1-PAD1-PadNC1)") (class "Default")
      (node (ref "J1") (pin "NC1") (pinfunction "PAD1_NC1") (pintype "bidirectional"))
    )
    (net (code "87") (name "unconnected-(J1-PAD2-PadNC2)") (class "Default")
      (node (ref "J1") (pin "NC2") (pinfunction "PAD2_NC2") (pintype "bidirectional"))
    )
    (net (code "88") (name "unconnected-(USB1-D+-Pad3-D+)") (class "Default")
      (node (ref "USB1") (pin "3-D+") (pinfunction "D+_3-D+") (pintype "bidirectional"))
    )
    (net (code "89") (name "unconnected-(USB1-D--Pad2-D-)") (class "Default")
      (node (ref "USB1") (pin "2-D-") (pinfunction "D-_2-D-") (pintype "bidirectional"))
    )
    (net (code "90") (name "unconnected-(USB1-ID-Pad4-ID)") (class "Default")
      (node (ref "USB1") (pin "4-ID") (pinfunction "ID_4-ID") (pintype "bidirectional"))
    )
    (net (code "91") (name "{slash}RST") (class "Default")
      (node (ref "IC5") (pin "29") (pinfunction "PC6(/RST)_29") (pintype "bidirectional"))
      (node (ref "J4") (pin "5") (pinfunction "5_5") (pintype "passive"))
      (node (ref "R9") (pin "1") (pinfunction "1_1") (pintype "passive"))
    )
  )
)
